# power.net
KiCad netlist of a schematic drawn in Altium Designer
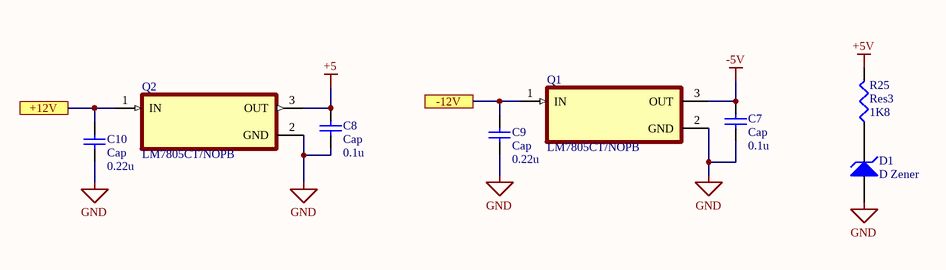
[diagram p0: power.SchDoc]

(export (version "E")
  (design (tool "Eeschema 10.0.6"))
  (components
    (comp (ref "C7")
      (value "Cap")
      (footprint "RAD-0.3")
      (description "Capacitor")
      (fields (field (name "ALTIUM_VALUE") "0.1u") (field (name "PUBLISHER") "Altium Limited"))
      (libsource (lib "Miscellaneous Devices") (part "Cap"))
    )
    (comp (ref "C8")
      (value "Cap")
      (footprint "RAD-0.3")
      (description "Capacitor")
      (fields (field (name "ALTIUM_VALUE") "0.1u") (field (name "PUBLISHER") "Altium Limited"))
      (libsource (lib "Miscellaneous Devices") (part "Cap"))
    )
    (comp (ref "C9")
      (value "Cap")
      (footprint "RAD-0.3")
      (description "Capacitor")
      (fields (field (name "ALTIUM_VALUE") "0.22u") (field (name "PUBLISHER") "Altium Limited"))
      (libsource (lib "Miscellaneous Devices") (part "Cap"))
    )
    (comp (ref "C10")
      (value "Cap")
      (footprint "RAD-0.3")
      (description "Capacitor")
      (fields (field (name "ALTIUM_VALUE") "0.22u") (field (name "PUBLISHER") "Altium Limited"))
      (libsource (lib "Miscellaneous Devices") (part "Cap"))
    )
    (comp (ref "D1")
      (value "D Zener")
      (footprint "DIODE-0.7")
      (description "Zener Diode")
      (fields (field (name "PUBLISHER") "Altium Limited"))
      (libsource (lib "Miscellaneous Devices") (part "D Zener"))
    )
    (comp (ref "Q1")
      (value "LM7805CT/NOPB")
      (footprint "TO254P1054X470X1955-3")
      (description "1.5-A, 30-V, linear voltage regulator 3-TO-220 0 to 125")
      (fields (field (name "MF") "Texas Instruments"))
      (libsource (lib "LM7805CT_NOPB") (part "LM7805CT/NOPB"))
    )
    (comp (ref "Q2")
      (value "LM7805CT/NOPB")
      (footprint "TO254P1054X470X1955-3")
      (description "1.5-A, 30-V, linear voltage regulator 3-TO-220 0 to 125")
      (fields (field (name "MF") "Texas Instruments"))
      (libsource (lib "LM7805CT_NOPB") (part "LM7805CT/NOPB"))
    )
    (comp (ref "R25")
      (value "Res3")
      (footprint "J1-0603")
      (description "Resistor")
      (fields (field (name "ALTIUM_VALUE") "1K8") (field (name "PUBLISHER") "Altium Limited"))
      (libsource (lib "Miscellaneous Devices") (part "Res3"))
    )
  )
  (nets
    (net (code "1") (name "+5") (class "Default")
      (node (ref "C8") (pin "2") (pinfunction "2_2") (pintype "passive"))
      (node (ref "Q2") (pin "3") (pinfunction "OUT_3") (pintype "output"))
    )
    (net (code "2") (name "+5V") (class "Default")
      (node (ref "R25") (pin "2") (pinfunction "2_2") (pintype "passive"))
    )
    (net (code "3") (name "-5V") (class "Default")
      (node (ref "C7") (pin "2") (pinfunction "2_2") (pintype "passive"))
      (node (ref "Q1") (pin "3") (pinfunction "OUT_3") (pintype "output"))
    )
    (net (code "4") (name "/+12V") (class "Default")
      (node (ref "C10") (pin "2") (pinfunction "2_2") (pintype "passive"))
      (node (ref "Q2") (pin "1") (pinfunction "IN_1") (pintype "input"))
    )
    (net (code "5") (name "/-12V") (class "Default")
      (node (ref "C9") (pin "2") (pinfunction "2_2") (pintype "passive"))
      (node (ref "Q1") (pin "1") (pinfunction "IN_1") (pintype "input"))
    )
    (net (code "6") (name "GND") (class "Default")
      (node (ref "C10") (pin "1") (pinfunction "1_1") (pintype "passive"))
      (node (ref "C7") (pin "1") (pinfunction "1_1") (pintype "passive"))
      (node (ref "C8") (pin "1") (pinfunction "1_1") (pintype "passive"))
      (node (ref "C9") (pin "1") (pinfunction "1_1") (pintype "passive"))
      (node (ref "D1") (pin "1") (pinfunction "A_1") (pintype "passive"))
      (node (ref "Q1") (pin "2") (pinfunction "GND_2") (pintype "power_in"))
      (node (ref "Q2") (pin "2") (pinfunction "GND_2") (pintype "power_in"))
    )
    (net (code "7") (name "Net-(D1-K)") (class "Default")
      (node (ref "D1") (pin "2") (pinfunction "K_2") (pintype "passive"))
      (node (ref "R25") (pin "1") (pinfunction "1_1") (pintype "passive"))
    )
  )
)
